# CTR-Lower-Main-Board-Rev-C-Power-3.net
KiCad netlist of a schematic drawn in Altium Designer
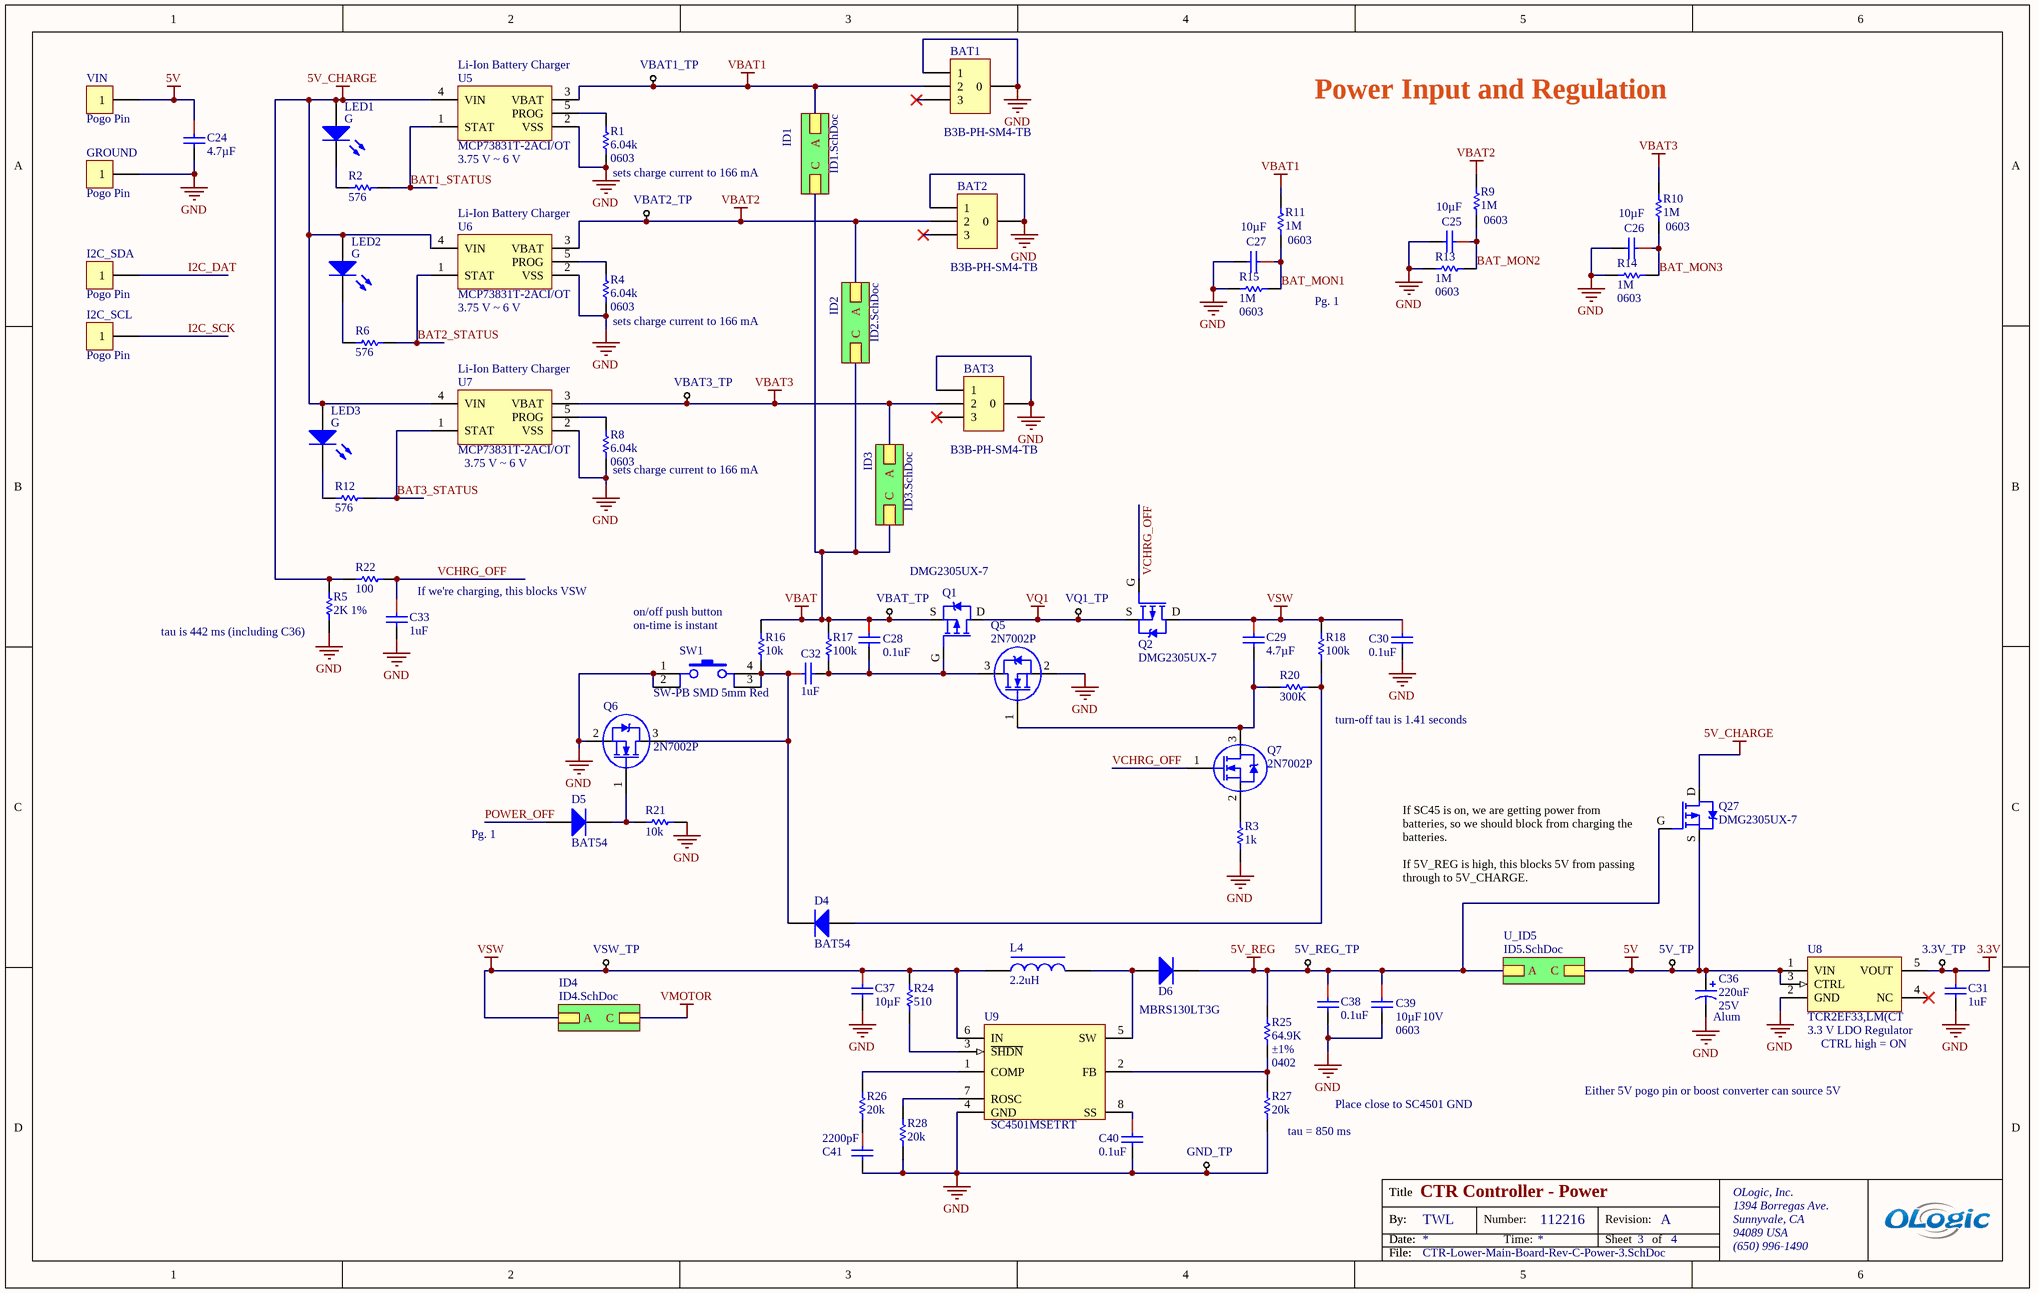
[diagram p0: CTR-Lower-Main-Board-Rev-C-Power-3.SchDoc]

(export (version "E")
  (design (tool "Eeschema 10.0.6"))
  (components
    (comp (ref "3.3V_TP")
      (value "3V")
      (footprint "TestPoint-TH 35 mil")
      (description "Test Point")
      (libsource (lib "OLogic-Misc") (part "TestPoint, small"))
    )
    (comp (ref "5V_REG_TP")
      (value "Test Point")
      (footprint "TestPoint-TH 42 mil")
      (libsource (lib "OLogic-Misc") (part "TestPoint, small"))
    )
    (comp (ref "5V_TP")
      (value "Test Point")
      (footprint "TestPoint-TH 42 mil")
      (libsource (lib "OLogic-Misc") (part "TestPoint, small"))
    )
    (comp (ref "BAT1")
      (value "B3B-PH-SM4-TB")
      (footprint "JST-B3B-PH-SM4-TB")
      (description "2mm Locking Header, 3-Pin")
      (fields
        (field (name "MANUFACTURER") "JST Sales America Inc")
        (field (name "MANUFACTURER PART NUMBER") "B3B-PH-SM4-TB(LF)(SN)(P)")
      )
      (libsource (lib "OLogic-Connectors") (part "JST-B3B-PH-SM4-TB"))
    )
    (comp (ref "BAT2")
      (value "B3B-PH-SM4-TB")
      (footprint "JST-B3B-PH-SM4-TB")
      (description "2mm Locking Header, 3-Pin")
      (fields
        (field (name "MANUFACTURER") "JST Sales America Inc")
        (field (name "MANUFACTURER PART NUMBER") "B3B-PH-SM4-TB(LF)(SN)(P)")
      )
      (libsource (lib "OLogic-Connectors") (part "JST-B3B-PH-SM4-TB"))
    )
    (comp (ref "BAT3")
      (value "B3B-PH-SM4-TB")
      (footprint "JST-B3B-PH-SM4-TB")
      (description "2mm Locking Header, 3-Pin")
      (fields
        (field (name "MANUFACTURER") "JST Sales America Inc")
        (field (name "MANUFACTURER PART NUMBER") "B3B-PH-SM4-TB(LF)(SN)(P)")
      )
      (libsource (lib "OLogic-Connectors") (part "JST-B3B-PH-SM4-TB"))
    )
    (comp (ref "C24")
      (value "4.7UF 0603")
      (footprint "CAPC0603(1608)_L")
      (fields
        (field (name "MANUFACTURER") "Taiyo Yuden")
        (field (name "MANUFACTURER PART NUMBER") "EMK107ABJ475KA-T")
        (field (name "TOLERANCE") "±10%")
        (field (name "CAPACITANCE") "4.7µF")
        (field (name "CREATOR") "osman")
      )
      (libsource (lib "OLogic-Passive") (part "CAP CER 4.7UF 16V 10% X5R 0603"))
    )
    (comp (ref "C25")
      (value "CAP 10UF 10V 10% X5R 0603")
      (footprint "CAPC0603(1608)_N")
      (description "10uF 0603")
      (fields
        (field (name "MANUFACTURER") "Samsung Electro-Mechanics America, Inc")
        (field (name "MANUFACTURER PART NUMBER") "CL10A106KP8NNNC")
        (field (name "CAPACITANCE") "10µF")
        (field (name "CREATOR") "osman")
      )
      (libsource (lib "OLogic-Passive") (part "CAP 10UF 10V 10% X5R 0603"))
    )
    (comp (ref "C26")
      (value "CAP 10UF 10V 10% X5R 0603")
      (footprint "CAPC0603(1608)_N")
      (description "10uF 0603")
      (fields
        (field (name "MANUFACTURER") "Samsung Electro-Mechanics America, Inc")
        (field (name "MANUFACTURER PART NUMBER") "CL10A106KP8NNNC")
        (field (name "CAPACITANCE") "10µF")
        (field (name "CREATOR") "osman")
      )
      (libsource (lib "OLogic-Passive") (part "CAP 10UF 10V 10% X5R 0603"))
    )
    (comp (ref "C27")
      (value "CAP 10UF 10V 10% X5R 0603")
      (footprint "CAPC0603(1608)_N")
      (description "10uF 0603")
      (fields
        (field (name "MANUFACTURER") "Samsung Electro-Mechanics America, Inc")
        (field (name "MANUFACTURER PART NUMBER") "CL10A106KP8NNNC")
        (field (name "CAPACITANCE") "10µF")
        (field (name "CREATOR") "osman")
      )
      (libsource (lib "OLogic-Passive") (part "CAP 10UF 10V 10% X5R 0603"))
    )
    (comp (ref "C28")
      (value "0.1uF")
      (footprint "CAPC0402(1005)_N")
      (description "0.1uF 0402 50V")
      (fields
        (field (name "MANUFACTURER") "TDK Corporation")
        (field (name "MANUFACTURER PART NUMBER") "CGA2B3X7R1H104K050BB")
        (field (name "CREATOR") "osman")
      )
      (libsource (lib "OLogic-Passive") (part "CAP CER 0.1UF 50V 10% X7R 0402"))
    )
    (comp (ref "C29")
      (value "4.7UF 0603")
      (footprint "CAPC0603(1608)_L")
      (fields
        (field (name "MANUFACTURER") "Taiyo Yuden")
        (field (name "MANUFACTURER PART NUMBER") "EMK107ABJ475KA-T")
        (field (name "TOLERANCE") "±10%")
        (field (name "CAPACITANCE") "4.7µF")
        (field (name "CREATOR") "osman")
      )
      (libsource (lib "OLogic-Passive") (part "CAP CER 4.7UF 16V 10% X5R 0603"))
    )
    (comp (ref "C30")
      (value "0.1uF")
      (footprint "CAPC0402(1005)_N")
      (description "0.1uF 0402 50V")
      (fields
        (field (name "MANUFACTURER") "TDK Corporation")
        (field (name "MANUFACTURER PART NUMBER") "CGA2B3X7R1H104K050BB")
        (field (name "CREATOR") "osman")
      )
      (libsource (lib "OLogic-Passive") (part "CAP CER 0.1UF 50V 10% X7R 0402"))
    )
    (comp (ref "C31")
      (value "1uF")
      (footprint "CAPC0402(1005)_N")
      (description "1UF 0402")
      (fields
        (field (name "MANUFACTURER") "TDK Corporation")
        (field (name "MANUFACTURER PART NUMBER") "C1005X5R1C105K050BC")
      )
      (libsource (lib "OLogic-Passive") (part "CAP CER 1UF 16V 10% X5R 0402"))
    )
    (comp (ref "C32")
      (value "1uF")
      (footprint "CAPC0402(1005)_N")
      (description "1UF 0402")
      (fields
        (field (name "MANUFACTURER") "TDK Corporation")
        (field (name "MANUFACTURER PART NUMBER") "C1005X5R1C105K050BC")
      )
      (libsource (lib "OLogic-Passive") (part "CAP CER 1UF 16V 10% X5R 0402"))
    )
    (comp (ref "C33")
      (value "1uF")
      (footprint "CAPC0402(1005)_N")
      (description "1UF 0402")
      (fields
        (field (name "MANUFACTURER") "TDK Corporation")
        (field (name "MANUFACTURER PART NUMBER") "C1005X5R1C105K050BC")
      )
      (libsource (lib "OLogic-Passive") (part "CAP CER 1UF 16V 10% X5R 0402"))
    )
    (comp (ref "C36")
      (value "220uF")
      (footprint "Panasonic-F-Ecap")
      (description "220uF F-SM")
      (fields
        (field (name "MANUFACTURER") "Panasonic")
        (field (name "MANUFACTURER PART NUMBER") "EEE-1EA221UP")
        (field (name "VOLTAGE RATING") "25V")
        (field (name "TEXT") "Alum")
      )
      (libsource (lib "OLogic-Passive") (part "CAP ALUM 220UF 25V 20% SMD"))
    )
    (comp (ref "C37")
      (value "CAP 10UF 10V 10% X5R 0603")
      (footprint "CAPC0603(1608)_N")
      (description "10uF 0603")
      (fields
        (field (name "MANUFACTURER") "Samsung Electro-Mechanics America, Inc")
        (field (name "MANUFACTURER PART NUMBER") "CL10A106KP8NNNC")
        (field (name "CAPACITANCE") "10µF")
        (field (name "CREATOR") "osman")
      )
      (libsource (lib "OLogic-Passive") (part "CAP 10UF 10V 10% X5R 0603"))
    )
    (comp (ref "C38")
      (value "0.1uF")
      (footprint "CAPC0402(1005)_N")
      (description "0.1uF 0402 50V")
      (fields
        (field (name "MANUFACTURER") "TDK Corporation")
        (field (name "MANUFACTURER PART NUMBER") "CGA2B3X7R1H104K050BB")
        (field (name "CREATOR") "osman")
      )
      (libsource (lib "OLogic-Passive") (part "CAP CER 0.1UF 50V 10% X7R 0402"))
    )
    (comp (ref "C39")
      (value "CAP 10UF 10V 10% X5R 0603")
      (footprint "CAPC0603(1608)_N")
      (description "10uF 0603")
      (fields
        (field (name "MANUFACTURER") "Samsung Electro-Mechanics America, Inc")
        (field (name "MANUFACTURER PART NUMBER") "CL10A106KP8NNNC")
        (field (name "VOLTAGE - RATED") "10V")
        (field (name "PACKAGE / CASE") "0603")
        (field (name "CAPACITANCE") "10µF")
        (field (name "CREATOR") "osman")
      )
      (libsource (lib "OLogic-Passive") (part "CAP 10UF 10V 10% X5R 0603"))
    )
    (comp (ref "C40")
      (value "0.1uF")
      (footprint "CAPC0402(1005)_N")
      (description "0.1uF 0402 50V")
      (fields
        (field (name "MANUFACTURER") "TDK Corporation")
        (field (name "MANUFACTURER PART NUMBER") "CGA2B3X7R1H104K050BB")
        (field (name "CREATOR") "osman")
      )
      (libsource (lib "OLogic-Passive") (part "CAP CER 0.1UF 50V 10% X7R 0402"))
    )
    (comp (ref "C41")
      (value "2200pF")
      (footprint "CAPC0402(1005)_N")
      (description "2200pF 0402")
      (fields
        (field (name "MANUFACTURER") "Yageo")
        (field (name "MANUFACTURER PART NUMBER") "CC0402KRX7R9BB222")
        (field (name "CAPACITANCE") "2200pF")
        (field (name "CREATOR") "osman")
      )
      (libsource (lib "OLogic-Passive") (part "CAP CER 2200PF 50V 10% X7R 0402"))
    )
    (comp (ref "D4")
      (value "BAT54")
      (footprint "SOT23")
      (description "Schottky Barrier Diode")
      (fields (field (name "MANUFACTURER") "Fairchild"))
      (libsource (lib "OLogic-Diode-Opto-LED") (part "BAT54"))
    )
    (comp (ref "D5")
      (value "BAT54")
      (footprint "SOT23")
      (description "Schottky Barrier Diode")
      (fields (field (name "MANUFACTURER") "Fairchild"))
      (libsource (lib "OLogic-Diode-Opto-LED") (part "BAT54"))
    )
    (comp (ref "D6")
      (value "MBRS130LT3")
      (footprint "DO-214AA")
      (description "Schottky Barrier Rectifier 1A 30V")
      (fields
        (field (name "MANUFACTURER") "ON Semiconductor")
        (field (name "MANUFACTURER PART NUMBER") "MBRS130LT3G")
      )
      (libsource (lib "OLogic-Diode-Opto-LED") (part "MBRS130LT3"))
    )
    (comp (ref "GND_TP")
      (value "GND")
      (footprint "TestPoint-TH 35 mil")
      (description "Test Point")
      (libsource (lib "OLogic-Misc") (part "TestPoint, small"))
    )
    (comp (ref "GROUND")
      (value "Pogo Pin")
      (footprint "POGO_PIN")
      (fields
        (field (name "MANUFACTURER") "Mill-Max Manufacturing Corp.")
        (field (name "MANUFACTURER PART NUMBER") "0850-0-15-20-83-14-11-0")
      )
      (libsource (lib "OLogic-Connectors") (part "0850-0-15-20-83-14-11-0"))
    )
    (comp (ref "I2C_SCL")
      (value "Pogo Pin")
      (footprint "POGO_PIN")
      (fields
        (field (name "MANUFACTURER") "Mill-Max Manufacturing Corp.")
        (field (name "MANUFACTURER PART NUMBER") "0850-0-15-20-83-14-11-0")
      )
      (libsource (lib "OLogic-Connectors") (part "0850-0-15-20-83-14-11-0"))
    )
    (comp (ref "I2C_SDA")
      (value "Pogo Pin")
      (footprint "POGO_PIN")
      (fields
        (field (name "MANUFACTURER") "Mill-Max Manufacturing Corp.")
        (field (name "MANUFACTURER PART NUMBER") "0850-0-15-20-83-14-11-0")
      )
      (libsource (lib "OLogic-Connectors") (part "0850-0-15-20-83-14-11-0"))
    )
    (comp (ref "L4")
      (value "2.2uH")
      (footprint "6x6SMINDC")
      (description "2.2uH 6x6mm")
      (fields
        (field (name "MANUFACTURER") "Taiyo Yuden")
        (field (name "MANUFACTURER PART NUMBER") "NR6028T2R2N")
      )
      (libsource (lib "OLogic-Passive") (part "INDUCTOR 2.2UH 4.2A 30% SMD"))
    )
    (comp (ref "LED1")
      (value "G")
      (footprint "SM-LED-0603")
      (description "0603 SMD GREEN LED")
      (fields
        (field (name "MANUFACTURER") "Lite-On Inc")
        (field (name "MANUFACTURER PART NUMBER") "LTST-C191KGKT")
      )
      (libsource (lib "OLogic-Diode-Opto-LED") (part "LED GREEN CLEAR THIN 0603 SMD"))
    )
    (comp (ref "LED2")
      (value "G")
      (footprint "SM-LED-0603")
      (description "0603 SMD GREEN LED")
      (fields
        (field (name "MANUFACTURER") "Lite-On Inc")
        (field (name "MANUFACTURER PART NUMBER") "LTST-C191KGKT")
      )
      (libsource (lib "OLogic-Diode-Opto-LED") (part "LED GREEN CLEAR THIN 0603 SMD"))
    )
    (comp (ref "LED3")
      (value "G")
      (footprint "SM-LED-0603")
      (description "0603 SMD GREEN LED")
      (fields
        (field (name "MANUFACTURER") "Lite-On Inc")
        (field (name "MANUFACTURER PART NUMBER") "LTST-C191KGKT")
      )
      (libsource (lib "OLogic-Diode-Opto-LED") (part "LED GREEN CLEAR THIN 0603 SMD"))
    )
    (comp (ref "Q1")
      (value "DMG2305UX")
      (footprint "DMG2305UX-7")
      (description "MOSFET P-CH 20V 4.2A SOT23")
      (fields
        (field (name "MANUFACTURER") "Diodes Incorporated")
        (field (name "MANUFACTURER PART NUMBER") "DMG2305UX-7")
        (field (name "CREATOR") "osman")
      )
      (libsource (lib "OLogic-Trans-Drivers") (part "DMG2305UX"))
    )
    (comp (ref "Q2")
      (value "DMG2305UX")
      (footprint "DMG2305UX-7")
      (description "MOSFET P-CH 20V 4.2A SOT23")
      (fields
        (field (name "MANUFACTURER") "Diodes Incorporated")
        (field (name "MANUFACTURER PART NUMBER") "DMG2305UX-7")
        (field (name "CREATOR") "osman")
      )
      (libsource (lib "OLogic-Trans-Drivers") (part "DMG2305UX"))
    )
    (comp (ref "Q5")
      (value "2N7002P")
      (footprint "SOT23")
      (description "MOSFET N-CH 60V 0.36A SOT-23")
      (fields
        (field (name "MANUFACTURER") "NXP Semiconductors")
        (field (name "MANUFACTURER PART NUMBER") "2N7002P,235")
      )
      (libsource (lib "") (part "2N7002P_2"))
    )
    (comp (ref "Q6")
      (value "2N7002P")
      (footprint "SOT23")
      (description "MOSFET N-CH 60V 0.36A SOT-23")
      (fields
        (field (name "MANUFACTURER") "NXP Semiconductors")
        (field (name "MANUFACTURER PART NUMBER") "2N7002P,235")
      )
      (libsource (lib "") (part "2N7002P_1"))
    )
    (comp (ref "Q7")
      (value "2N7002P")
      (footprint "SOT23")
      (description "MOSFET N-CH 60V 0.36A SOT-23")
      (fields
        (field (name "MANUFACTURER") "NXP Semiconductors")
        (field (name "MANUFACTURER PART NUMBER") "2N7002P,235")
      )
      (libsource (lib "OLogic-Trans-Drivers") (part "2N7002P"))
    )
    (comp (ref "Q27")
      (value "DMG2305UX")
      (footprint "DMG2305UX-7")
      (description "MOSFET P-CH 20V 4.2A SOT23")
      (fields
        (field (name "MANUFACTURER") "Diodes Incorporated")
        (field (name "MANUFACTURER PART NUMBER") "DMG2305UX-7")
        (field (name "CREATOR") "osman")
      )
      (libsource (lib "OLogic-Trans-Drivers") (part "DMG2305UX"))
    )
    (comp (ref "R1")
      (value "6.04k")
      (footprint "RESC0603(1608)_N")
      (description "6.04K 0603 RNCP0603FTD6K04")
      (fields
        (field (name "MANUFACTURER") "Stackpole Electronics Inc.")
        (field (name "MANUFACTURER PART NUMBER") "RNCP0603FTD6K04")
        (field (name "SUPPLIER DEVICE PACKAGE") "0603")
      )
      (libsource (lib "OLogic-Passive") (part "RES 6.04K OHM 1/8W 1% 0603"))
    )
    (comp (ref "R2")
      (value "576")
      (footprint "RESC0402(1005)_N")
      (description "575 0402")
      (fields
        (field (name "MANUFACTURER") "Panasonic Electronic Components")
        (field (name "MANUFACTURER PART NUMBER") "ERJ-2RKF5760X")
        (field (name "RESISTANCE (OHMS)") "576")
        (field (name "CREATOR") "osman")
      )
      (libsource (lib "OLogic-Passive") (part "RES 576 OHM 1% 1/10W 0402"))
    )
    (comp (ref "R3")
      (value "1K")
      (footprint "RESC0402(1005)_N")
      (description "1K 0402")
      (fields
        (field (name "MANUFACTURER") "Panasonic Electronic Components")
        (field (name "MANUFACTURER PART NUMBER") "ERJ-2RKF1001X")
        (field (name "RESISTANCE (OHMS)") "1k")
        (field (name "CREATOR") "osman")
      )
      (libsource (lib "OLogic-Passive") (part "RES 1K OHM 1% 1/10W 0402"))
    )
    (comp (ref "R4")
      (value "6.04k")
      (footprint "RESC0603(1608)_N")
      (description "6.04K 0603 RNCP0603FTD6K04")
      (fields
        (field (name "MANUFACTURER") "Stackpole Electronics Inc.")
        (field (name "MANUFACTURER PART NUMBER") "RNCP0603FTD6K04")
        (field (name "SUPPLIER DEVICE PACKAGE") "0603")
      )
      (libsource (lib "OLogic-Passive") (part "RES 6.04K OHM 1/8W 1% 0603"))
    )
    (comp (ref "R5")
      (value "2K 1%")
      (footprint "RESC0402(1005)_N")
      (description "2K 1% 0402")
      (fields
        (field (name "MANUFACTURER") "Panasonic Electronic Components")
        (field (name "MANUFACTURER PART NUMBER") "ERJ-2RKF2001X")
      )
      (libsource (lib "OLogic-Passive") (part "RES 2K OHM 1% 1/10W 0402"))
    )
    (comp (ref "R6")
      (value "576")
      (footprint "RESC0402(1005)_N")
      (description "575 0402")
      (fields
        (field (name "MANUFACTURER") "Panasonic Electronic Components")
        (field (name "MANUFACTURER PART NUMBER") "ERJ-2RKF5760X")
        (field (name "RESISTANCE (OHMS)") "576")
        (field (name "CREATOR") "osman")
      )
      (libsource (lib "OLogic-Passive") (part "RES 576 OHM 1% 1/10W 0402"))
    )
    (comp (ref "R8")
      (value "6.04k")
      (footprint "RESC0603(1608)_N")
      (description "6.04K 0603 RNCP0603FTD6K04")
      (fields
        (field (name "MANUFACTURER") "Stackpole Electronics Inc.")
        (field (name "MANUFACTURER PART NUMBER") "RNCP0603FTD6K04")
        (field (name "SUPPLIER DEVICE PACKAGE") "0603")
      )
      (libsource (lib "OLogic-Passive") (part "RES 6.04K OHM 1/8W 1% 0603"))
    )
    (comp (ref "R9")
      (value "1M")
      (footprint "RESC0603(1608)_N")
      (description "1M 0603")
      (fields
        (field (name "MANUFACTURER") "Panasonic Electronic Components")
        (field (name "MANUFACTURER PART NUMBER") "ERJ-3EKF1004V")
        (field (name "SUPPLIER DEVICE PACKAGE") "0603")
      )
      (libsource (lib "OLogic-Passive") (part "RES 1M OHM 1/10W 1% 0603 SMD"))
    )
    (comp (ref "R10")
      (value "1M")
      (footprint "RESC0603(1608)_N")
      (description "1M 0603")
      (fields
        (field (name "MANUFACTURER") "Panasonic Electronic Components")
        (field (name "MANUFACTURER PART NUMBER") "ERJ-3EKF1004V")
        (field (name "SUPPLIER DEVICE PACKAGE") "0603")
      )
      (libsource (lib "OLogic-Passive") (part "RES 1M OHM 1/10W 1% 0603 SMD"))
    )
    (comp (ref "R11")
      (value "1M")
      (footprint "RESC0603(1608)_N")
      (description "1M 0603")
      (fields
        (field (name "MANUFACTURER") "Panasonic Electronic Components")
        (field (name "MANUFACTURER PART NUMBER") "ERJ-3EKF1004V")
        (field (name "SUPPLIER DEVICE PACKAGE") "0603")
      )
      (libsource (lib "OLogic-Passive") (part "RES 1M OHM 1/10W 1% 0603 SMD"))
    )
    (comp (ref "R12")
      (value "576")
      (footprint "RESC0402(1005)_N")
      (description "575 0402")
      (fields
        (field (name "MANUFACTURER") "Panasonic Electronic Components")
        (field (name "MANUFACTURER PART NUMBER") "ERJ-2RKF5760X")
        (field (name "RESISTANCE (OHMS)") "576")
        (field (name "CREATOR") "osman")
      )
      (libsource (lib "OLogic-Passive") (part "RES 576 OHM 1% 1/10W 0402"))
    )
    (comp (ref "R13")
      (value "1M")
      (footprint "RESC0603(1608)_N")
      (description "1M 0603")
      (fields
        (field (name "MANUFACTURER") "Panasonic Electronic Components")
        (field (name "MANUFACTURER PART NUMBER") "ERJ-3EKF1004V")
        (field (name "SUPPLIER DEVICE PACKAGE") "0603")
      )
      (libsource (lib "OLogic-Passive") (part "RES 1M OHM 1/10W 1% 0603 SMD"))
    )
    (comp (ref "R14")
      (value "1M")
      (footprint "RESC0603(1608)_N")
      (description "1M 0603")
      (fields
        (field (name "MANUFACTURER") "Panasonic Electronic Components")
        (field (name "MANUFACTURER PART NUMBER") "ERJ-3EKF1004V")
        (field (name "SUPPLIER DEVICE PACKAGE") "0603")
      )
      (libsource (lib "OLogic-Passive") (part "RES 1M OHM 1/10W 1% 0603 SMD"))
    )
    (comp (ref "R15")
      (value "1M")
      (footprint "RESC0603(1608)_N")
      (description "1M 0603")
      (fields
        (field (name "MANUFACTURER") "Panasonic Electronic Components")
        (field (name "MANUFACTURER PART NUMBER") "ERJ-3EKF1004V")
        (field (name "SUPPLIER DEVICE PACKAGE") "0603")
      )
      (libsource (lib "OLogic-Passive") (part "RES 1M OHM 1/10W 1% 0603 SMD"))
    )
    (comp (ref "R16")
      (value "10K")
      (footprint "RESC0402(1005)_N")
      (description "10K 0402")
      (fields
        (field (name "MANUFACTURER") "Panasonic Electronic Components")
        (field (name "MANUFACTURER PART NUMBER") "ERJ-2RKF1002X")
        (field (name "RESISTANCE (OHMS)") "10k")
        (field (name "CREATOR") "osman")
      )
      (libsource (lib "OLogic-Passive") (part "RES 10K OHM 1% 1/10W 0402"))
    )
    (comp (ref "R17")
      (value "100K 0402")
      (footprint "RESC0402(1005)_N")
      (fields
        (field (name "MANUFACTURER") "Panasonic Electronic Components")
        (field (name "MANUFACTURER PART NUMBER") "ERJ-2RKF1003X")
        (field (name "TOLERANCE") "±1%")
        (field (name "RESISTANCE (OHMS)") "100k")
        (field (name "CREATOR") "osman")
      )
      (libsource (lib "OLogic-Passive") (part "RES 100K OHM 1% 1/10W 0402"))
    )
    (comp (ref "R18")
      (value "100K 0402")
      (footprint "RESC0402(1005)_N")
      (fields
        (field (name "MANUFACTURER") "Panasonic Electronic Components")
        (field (name "MANUFACTURER PART NUMBER") "ERJ-2RKF1003X")
        (field (name "TOLERANCE") "±1%")
        (field (name "RESISTANCE (OHMS)") "100k")
        (field (name "CREATOR") "osman")
      )
      (libsource (lib "OLogic-Passive") (part "RES 100K OHM 1% 1/10W 0402"))
    )
    (comp (ref "R20")
      (value "300K")
      (footprint "RESC0402(1005)_N")
      (description "300K 0402")
      (fields
        (field (name "MANUFACTURER") "Panasonic Electronic Components")
        (field (name "MANUFACTURER PART NUMBER") "ERJ-2RKF3003X")
      )
      (libsource (lib "OLogic-Passive") (part "RES 300K OHM 1% 1/10W 0402"))
    )
    (comp (ref "R21")
      (value "10K")
      (footprint "RESC0402(1005)_N")
      (description "10K 0402")
      (fields
        (field (name "MANUFACTURER") "Panasonic Electronic Components")
        (field (name "MANUFACTURER PART NUMBER") "ERJ-2RKF1002X")
        (field (name "RESISTANCE (OHMS)") "10k")
        (field (name "CREATOR") "osman")
      )
      (libsource (lib "OLogic-Passive") (part "RES 10K OHM 1% 1/10W 0402"))
    )
    (comp (ref "R22")
      (value "100 0402")
      (footprint "RESC0402(1005)_N")
      (fields
        (field (name "MANUFACTURER") "Panasonic Electronic Components")
        (field (name "MANUFACTURER PART NUMBER") "ERJ-2RKF1000X")
        (field (name "TOLERANCE") "±1%")
        (field (name "RESISTANCE (OHMS)") "100")
        (field (name "CREATOR") "osman")
      )
      (libsource (lib "OLogic-Passive") (part "RES 100 OHM 1% 1/10W 0402"))
    )
    (comp (ref "R24")
      (value "510")
      (footprint "RESC0603(1608)_N")
      (description "510 0603")
      (fields
        (field (name "MANUFACTURER") "Panasonic Electronic Components")
        (field (name "MANUFACTURER PART NUMBER") "ERJ-3EKF5100V")
      )
      (libsource (lib "OLogic-Passive") (part "RES 510 OHM 1/10W 1% 0603 SMD"))
    )
    (comp (ref "R25")
      (value "64.9K")
      (footprint "RESC0402(1005)_N")
      (description "RES 64.9K OHM 1% 1/10W 0402")
      (fields
        (field (name "MANUFACTURER") "Panasonic Electronic Components")
        (field (name "MANUFACTURER PART NUMBER") "ERJ-2RKF6492X")
        (field (name "TOLERANCE") "±1%")
        (field (name "SUPPLIER DEVICE PACKAGE") "0402")
      )
      (libsource (lib "OLogic-Passive") (part "RES 64.9K OHM 1% 1/10W 0402"))
    )
    (comp (ref "R26")
      (value "20K 0402")
      (footprint "RESC0402(1005)_N")
      (fields
        (field (name "MANUFACTURER") "Panasonic Electronic Components")
        (field (name "MANUFACTURER PART NUMBER") "ERJ-2RKF2002X")
        (field (name "RESISTANCE (OHMS)") "20k")
        (field (name "TOLERANCE") "±1%")
      )
      (libsource (lib "OLogic-Passive") (part "RES 20K OHM 1% 1/10W 0402"))
    )
    (comp (ref "R27")
      (value "20K 0402")
      (footprint "RESC0402(1005)_N")
      (fields
        (field (name "MANUFACTURER") "Panasonic Electronic Components")
        (field (name "MANUFACTURER PART NUMBER") "ERJ-2RKF2002X")
        (field (name "TOLERANCE") "±1%")
        (field (name "RESISTANCE (OHMS)") "20k")
      )
      (libsource (lib "OLogic-Passive") (part "RES 20K OHM 1% 1/10W 0402"))
    )
    (comp (ref "R28")
      (value "20K 0402")
      (footprint "RESC0402(1005)_N")
      (fields
        (field (name "MANUFACTURER") "Panasonic Electronic Components")
        (field (name "MANUFACTURER PART NUMBER") "ERJ-2RKF2002X")
        (field (name "RESISTANCE (OHMS)") "20k")
        (field (name "TOLERANCE") "±1%")
      )
      (libsource (lib "OLogic-Passive") (part "RES 20K OHM 1% 1/10W 0402"))
    )
    (comp (ref "SW1")
      (value "SW-PB SMD 5mm Red")
      (footprint "SW TACT Red 6mm x 6mm")
      (description "SWITCH TACTILE SPST-NO 0.05A 12V")
      (fields
        (field (name "MANUFACTURER") "C&K Components")
        (field (name "MANUFACTURER PART NUMBER") "PTS645SK50SMTR92 LFS")
        (field (name "PUBLISHER") "Altium Limited")
      )
      (libsource (lib "OLogic-Switches") (part "SW-PB SMD 5mm Red"))
    )
    (comp (ref "U5")
      (value "Li-Ion Battery Charger")
      (footprint "SOT23-5")
      (fields
        (field (name "MPN") "MCP73831T")
        (field (name "MANUFACTURER") "Microchip")
        (field (name "MANUFACTURER PART NUMBER") "MCP73831T-2ACI/OT")
        (field (name "VOLTAGE - SUPPLY") "3.75 V ~ 6 V")
      )
      (libsource (lib "OLogic-Misc") (part "MCP73831"))
    )
    (comp (ref "U6")
      (value "Li-Ion Battery Charger")
      (footprint "SOT23-5")
      (fields
        (field (name "MPN") "MCP73831T")
        (field (name "MANUFACTURER") "Microchip")
        (field (name "MANUFACTURER PART NUMBER") "MCP73831T-2ACI/OT")
        (field (name "VOLTAGE - SUPPLY") "3.75 V ~ 6 V")
      )
      (libsource (lib "OLogic-Misc") (part "MCP73831"))
    )
    (comp (ref "U7")
      (value "Li-Ion Battery Charger")
      (footprint "SOT23-5")
      (fields
        (field (name "MPN") "MCP73831T")
        (field (name "MANUFACTURER") "Microchip")
        (field (name "MANUFACTURER PART NUMBER") "MCP73831T-2ACI/OT")
        (field (name "VOLTAGE - SUPPLY") "3.75 V ~ 6 V")
      )
      (libsource (lib "OLogic-Misc") (part "MCP73831"))
    )
    (comp (ref "U8")
      (value "3.3 V LDO Regulator")
      (footprint "TCRFEF")
      (description "IC REG LDO 3.3V 0.2A ESV")
      (fields
        (field (name "MANUFACTURER") "Toshiba Semiconductor and Storage")
        (field (name "MANUFACTURER PART NUMBER") "TCR2EF33,LM(CT")
        (field (name "CREATOR") "osman")
      )
      (libsource (lib "OLogic-Reg-Convert") (part "TCR2EF33"))
    )
    (comp (ref "U9")
      (value "SC4501")
      (footprint "SC4501")
      (description "2A Switching Step-Up Regulator")
      (fields
        (field (name "MANUFACTURER") "Semtech Corporation")
        (field (name "MANUFACTURER PART NUMBER") "SC4501MSETRT")
      )
      (libsource (lib "OLogic-Reg-Convert") (part "SC4501"))
    )
    (comp (ref "VBAT1_TP")
      (value "Test Point")
      (footprint "TestPoint-TH 42 mil")
      (libsource (lib "OLogic-Misc") (part "TestPoint, small"))
    )
    (comp (ref "VBAT2_TP")
      (value "Test Point")
      (footprint "TestPoint-TH 42 mil")
      (libsource (lib "OLogic-Misc") (part "TestPoint, small"))
    )
    (comp (ref "VBAT3_TP")
      (value "Test Point")
      (footprint "TestPoint-TH 42 mil")
      (libsource (lib "OLogic-Misc") (part "TestPoint, small"))
    )
    (comp (ref "VBAT_TP")
      (value "Test Point")
      (footprint "TestPoint-TH 42 mil")
      (libsource (lib "OLogic-Misc") (part "TestPoint, small"))
    )
    (comp (ref "VIN")
      (value "Pogo Pin")
      (footprint "POGO_PIN")
      (fields
        (field (name "MANUFACTURER") "Mill-Max Manufacturing Corp.")
        (field (name "MANUFACTURER PART NUMBER") "0850-0-15-20-83-14-11-0")
      )
      (libsource (lib "OLogic-Connectors") (part "0850-0-15-20-83-14-11-0"))
    )
    (comp (ref "VQ1_TP")
      (value "Test Point")
      (footprint "TestPoint-TH 42 mil")
      (libsource (lib "OLogic-Misc") (part "TestPoint, small"))
    )
    (comp (ref "VSW_TP")
      (value "Test Point")
      (footprint "TestPoint-TH 42 mil")
      (libsource (lib "OLogic-Misc") (part "TestPoint, small"))
    )
  )
  (nets
    (net (code "1") (name "/BAT1_STATUS") (class "Default")
      (node (ref "R2") (pin "2") (pinfunction "2_2") (pintype "passive"))
      (node (ref "U5") (pin "1") (pinfunction "STAT_1") (pintype "passive"))
    )
    (net (code "2") (name "/BAT2_STATUS") (class "Default")
      (node (ref "R6") (pin "2") (pinfunction "2_2") (pintype "passive"))
      (node (ref "U6") (pin "1") (pinfunction "STAT_1") (pintype "passive"))
    )
    (net (code "3") (name "/BAT3_STATUS") (class "Default")
      (node (ref "R12") (pin "2") (pinfunction "2_2") (pintype "passive"))
      (node (ref "U7") (pin "1") (pinfunction "STAT_1") (pintype "passive"))
    )
    (net (code "4") (name "/BAT_MON1") (class "Default")
      (node (ref "C27") (pin "1") (pinfunction "1_1") (pintype "passive"))
      (node (ref "R11") (pin "1") (pinfunction "1_1") (pintype "passive"))
      (node (ref "R15") (pin "1") (pinfunction "1_1") (pintype "passive"))
    )
    (net (code "5") (name "/BAT_MON2") (class "Default")
      (node (ref "C25") (pin "1") (pinfunction "1_1") (pintype "passive"))
      (node (ref "R13") (pin "1") (pinfunction "1_1") (pintype "passive"))
      (node (ref "R9") (pin "1") (pinfunction "1_1") (pintype "passive"))
    )
    (net (code "6") (name "/BAT_MON3") (class "Default")
      (node (ref "C26") (pin "1") (pinfunction "1_1") (pintype "passive"))
      (node (ref "R10") (pin "1") (pinfunction "1_1") (pintype "passive"))
      (node (ref "R14") (pin "1") (pinfunction "1_1") (pintype "passive"))
    )
    (net (code "7") (name "/I2C_DAT") (class "Default")
      (node (ref "I2C_SDA") (pin "1") (pinfunction "1_1") (pintype "passive"))
    )
    (net (code "8") (name "/I2C_SCK") (class "Default")
      (node (ref "I2C_SCL") (pin "1") (pinfunction "1_1") (pintype "passive"))
    )
    (net (code "9") (name "/POWER_OFF") (class "Default")
      (node (ref "D5") (pin "1") (pinfunction "A_1") (pintype "passive"))
    )
    (net (code "10") (name "/VCHRG_OFF") (class "Default")
      (node (ref "C33") (pin "1") (pinfunction "1_1") (pintype "passive"))
      (node (ref "Q2") (pin "G") (pinfunction "G_G") (pintype "passive"))
      (node (ref "Q7") (pin "1") (pinfunction "G_1") (pintype "passive"))
      (node (ref "R22") (pin "1") (pinfunction "1_1") (pintype "passive"))
    )
    (net (code "11") (name "3.3V") (class "Default")
      (node (ref "3.3V_TP") (pin "1") (pinfunction "1_1") (pintype "passive"))
      (node (ref "C31") (pin "1") (pinfunction "1_1") (pintype "passive"))
      (node (ref "U8") (pin "5") (pinfunction "VOUT_5") (pintype "power_in"))
    )
    (net (code "12") (name "5V") (class "Default")
      (node (ref "5V_TP") (pin "1") (pinfunction "1_1") (pintype "passive"))
      (node (ref "C24") (pin "1") (pinfunction "1_1") (pintype "passive"))
      (node (ref "C36") (pin "1") (pinfunction "1_1") (pintype "passive"))
      (node (ref "Q27") (pin "S") (pinfunction "S_S") (pintype "passive"))
      (node (ref "U8") (pin "1") (pinfunction "VIN_1") (pintype "power_in"))
      (node (ref "U8") (pin "3") (pinfunction "CTRL_3") (pintype "input"))
      (node (ref "VIN") (pin "1") (pinfunction "1_1") (pintype "passive"))
    )
    (net (code "13") (name "5V_CHARGE") (class "Default")
      (node (ref "LED1") (pin "1") (pinfunction "1_1") (pintype "passive"))
      (node (ref "LED2") (pin "1") (pinfunction "1_1") (pintype "passive"))
      (node (ref "LED3") (pin "1") (pinfunction "1_1") (pintype "passive"))
      (node (ref "Q27") (pin "D") (pinfunction "D_D") (pintype "passive"))
      (node (ref "R22") (pin "2") (pinfunction "2_2") (pintype "passive"))
      (node (ref "R5") (pin "2") (pinfunction "2_2") (pintype "passive"))
      (node (ref "U5") (pin "4") (pinfunction "VIN_4") (pintype "passive"))
      (node (ref "U6") (pin "4") (pinfunction "VIN_4") (pintype "passive"))
      (node (ref "U7") (pin "4") (pinfunction "VIN_4") (pintype "passive"))
    )
    (net (code "14") (name "5V_REG") (class "Default")
      (node (ref "5V_REG_TP") (pin "1") (pinfunction "1_1") (pintype "passive"))
      (node (ref "C38") (pin "1") (pinfunction "1_1") (pintype "passive"))
      (node (ref "C39") (pin "1") (pinfunction "1_1") (pintype "passive"))
      (node (ref "D6") (pin "2") (pinfunction "K_2") (pintype "passive"))
      (node (ref "Q27") (pin "G") (pinfunction "G_G") (pintype "passive"))
      (node (ref "R25") (pin "2") (pinfunction "2_2") (pintype "passive"))
    )
    (net (code "15") (name "GND") (class "Default")
      (node (ref "BAT1") (pin "0") (pinfunction "0_0") (pintype "passive"))
      (node (ref "BAT1") (pin "1") (pinfunction "1_1") (pintype "passive"))
      (node (ref "BAT2") (pin "0") (pinfunction "0_0") (pintype "passive"))
      (node (ref "BAT2") (pin "1") (pinfunction "1_1") (pintype "passive"))
      (node (ref "BAT3") (pin "0") (pinfunction "0_0") (pintype "passive"))
      (node (ref "BAT3") (pin "1") (pinfunction "1_1") (pintype "passive"))
      (node (ref "C24") (pin "2") (pinfunction "2_2") (pintype "passive"))
      (node (ref "C25") (pin "2") (pinfunction "2_2") (pintype "passive"))
      (node (ref "C26") (pin "2") (pinfunction "2_2") (pintype "passive"))
      (node (ref "C27") (pin "2") (pinfunction "2_2") (pintype "passive"))
      (node (ref "C30") (pin "2") (pinfunction "2_2") (pintype "passive"))
      (node (ref "C31") (pin "2") (pinfunction "2_2") (pintype "passive"))
      (node (ref "C33") (pin "2") (pinfunction "2_2") (pintype "passive"))
      (node (ref "C36") (pin "2") (pinfunction "2_2") (pintype "passive"))
      (node (ref "C37") (pin "2") (pinfunction "2_2") (pintype "passive"))
      (node (ref "C38") (pin "2") (pinfunction "2_2") (pintype "passive"))
      (node (ref "C39") (pin "2") (pinfunction "2_2") (pintype "passive"))
      (node (ref "C40") (pin "2") (pinfunction "2_2") (pintype "passive"))
      (node (ref "C41") (pin "2") (pinfunction "2_2") (pintype "passive"))
      (node (ref "GND_TP") (pin "1") (pinfunction "1_1") (pintype "passive"))
      (node (ref "GROUND") (pin "1") (pinfunction "1_1") (pintype "passive"))
      (node (ref "Q5") (pin "2") (pinfunction "S_2") (pintype "passive"))
      (node (ref "Q6") (pin "2") (pinfunction "S_2") (pintype "passive"))
      (node (ref "R1") (pin "1") (pinfunction "1_1") (pintype "passive"))
      (node (ref "R13") (pin "2") (pinfunction "2_2") (pintype "passive"))
      (node (ref "R14") (pin "2") (pinfunction "2_2") (pintype "passive"))
      (node (ref "R15") (pin "2") (pinfunction "2_2") (pintype "passive"))
      (node (ref "R21") (pin "1") (pinfunction "1_1") (pintype "passive"))
      (node (ref "R27") (pin "1") (pinfunction "1_1") (pintype "passive"))
      (node (ref "R28") (pin "2") (pinfunction "2_2") (pintype "passive"))
      (node (ref "R3") (pin "1") (pinfunction "1_1") (pintype "passive"))
      (node (ref "R4") (pin "1") (pinfunction "1_1") (pintype "passive"))
      (node (ref "R5") (pin "1") (pinfunction "1_1") (pintype "passive"))
      (node (ref "R8") (pin "1") (pinfunction "1_1") (pintype "passive"))
      (node (ref "SW1") (pin "1") (pinfunction "1_1") (pintype "passive"))
      (node (ref "SW1") (pin "2") (pinfunction "2_2") (pintype "passive"))
      (node (ref "U5") (pin "2") (pinfunction "VSS_2") (pintype "passive"))
      (node (ref "U6") (pin "2") (pinfunction "VSS_2") (pintype "passive"))
      (node (ref "U7") (pin "2") (pinfunction "VSS_2") (pintype "passive"))
      (node (ref "U8") (pin "2") (pinfunction "GND_2") (pintype "power_in"))
      (node (ref "U9") (pin "4") (pinfunction "GND_4") (pintype "power_in"))
    )
    (net (code "16") (name "Net-(C41-Pad1)") (class "Default")
      (node (ref "C41") (pin "1") (pinfunction "1_1") (pintype "passive"))
      (node (ref "R26") (pin "2") (pinfunction "2_2") (pintype "passive"))
    )
    (net (code "17") (name "Net-(D4-A)") (class "Default")
      (node (ref "D4") (pin "1") (pinfunction "A_1") (pintype "passive"))
      (node (ref "R18") (pin "1") (pinfunction "1_1") (pintype "passive"))
      (node (ref "R20") (pin "1") (pinfunction "1_1") (pintype "passive"))
    )
    (net (code "18") (name "Net-(D4-K)") (class "Default")
      (node (ref "C32") (pin "1") (pinfunction "1_1") (pintype "passive"))
      (node (ref "D4") (pin "3") (pinfunction "K_3") (pintype "passive"))
      (node (ref "Q6") (pin "3") (pinfunction "D_3") (pintype "passive"))
      (node (ref "R16") (pin "1") (pinfunction "1_1") (pintype "passive"))
      (node (ref "SW1") (pin "3") (pinfunction "3_3") (pintype "passive"))
      (node (ref "SW1") (pin "4") (pinfunction "4_4") (pintype "passive"))
    )
    (net (code "19") (name "Net-(D5-K)") (class "Default")
      (node (ref "D5") (pin "3") (pinfunction "K_3") (pintype "passive"))
      (node (ref "Q6") (pin "1") (pinfunction "G_1") (pintype "passive"))
      (node (ref "R21") (pin "2") (pinfunction "2_2") (pintype "passive"))
    )
    (net (code "20") (name "Net-(D6-A)") (class "Default")
      (node (ref "D6") (pin "1") (pinfunction "A_1") (pintype "passive"))
      (node (ref "L4") (pin "2") (pinfunction "2_2") (pintype "passive"))
      (node (ref "U9") (pin "5") (pinfunction "SW_5") (pintype "passive"))
    )
    (net (code "21") (name "Net-(LED1-Pad2)") (class "Default")
      (node (ref "LED1") (pin "2") (pinfunction "2_2") (pintype "passive"))
      (node (ref "R2") (pin "1") (pinfunction "1_1") (pintype "passive"))
    )
    (net (code "22") (name "Net-(LED2-Pad2)") (class "Default")
      (node (ref "LED2") (pin "2") (pinfunction "2_2") (pintype "passive"))
      (node (ref "R6") (pin "1") (pinfunction "1_1") (pintype "passive"))
    )
    (net (code "23") (name "Net-(LED3-Pad2)") (class "Default")
      (node (ref "LED3") (pin "2") (pinfunction "2_2") (pintype "passive"))
      (node (ref "R12") (pin "1") (pinfunction "1_1") (pintype "passive"))
    )
    (net (code "24") (name "Net-(Q5-D)") (class "Default")
      (node (ref "C28") (pin "2") (pinfunction "2_2") (pintype "passive"))
      (node (ref "C32") (pin "2") (pinfunction "2_2") (pintype "passive"))
      (node (ref "Q1") (pin "G") (pinfunction "G_G") (pintype "passive"))
      (node (ref "Q5") (pin "3") (pinfunction "D_3") (pintype "passive"))
      (node (ref "R17") (pin "1") (pinfunction "1_1") (pintype "passive"))
    )
    (net (code "25") (name "Net-(Q5-G)") (class "Default")
      (node (ref "C29") (pin "2") (pinfunction "2_2") (pintype "passive"))
      (node (ref "Q5") (pin "1") (pinfunction "G_1") (pintype "passive"))
      (node (ref "Q7") (pin "3") (pinfunction "D_3") (pintype "passive"))
      (node (ref "R20") (pin "2") (pinfunction "2_2") (pintype "passive"))
    )
    (net (code "26") (name "Net-(Q7-S)") (class "Default")
      (node (ref "Q7") (pin "2") (pinfunction "S_2") (pintype "passive"))
      (node (ref "R3") (pin "2") (pinfunction "2_2") (pintype "passive"))
    )
    (net (code "27") (name "Net-(U5-PROG)") (class "Default")
      (node (ref "R1") (pin "2") (pinfunction "2_2") (pintype "passive"))
      (node (ref "U5") (pin "5") (pinfunction "PROG_5") (pintype "passive"))
    )
    (net (code "28") (name "Net-(U6-PROG)") (class "Default")
      (node (ref "R4") (pin "2") (pinfunction "2_2") (pintype "passive"))
      (node (ref "U6") (pin "5") (pinfunction "PROG_5") (pintype "passive"))
    )
    (net (code "29") (name "Net-(U7-PROG)") (class "Default")
      (node (ref "R8") (pin "2") (pinfunction "2_2") (pintype "passive"))
      (node (ref "U7") (pin "5") (pinfunction "PROG_5") (pintype "passive"))
    )
    (net (code "30") (name "Net-(U9-COMP)") (class "Default")
      (node (ref "R26") (pin "1") (pinfunction "1_1") (pintype "passive"))
      (node (ref "U9") (pin "1") (pinfunction "COMP_1") (pintype "passive"))
    )
    (net (code "31") (name "Net-(U9-FB)") (class "Default")
      (node (ref "R25") (pin "1") (pinfunction "1_1") (pintype "passive"))
      (node (ref "R27") (pin "2") (pinfunction "2_2") (pintype "passive"))
      (node (ref "U9") (pin "2") (pinfunction "FB_2") (pintype "passive"))
    )
    (net (code "32") (name "Net-(U9-ROSC)") (class "Default")
      (node (ref "R28") (pin "1") (pinfunction "1_1") (pintype "passive"))
      (node (ref "U9") (pin "7") (pinfunction "ROSC_7") (pintype "passive"))
    )
    (net (code "33") (name "Net-(U9-SS)") (class "Default")
      (node (ref "C40") (pin "1") (pinfunction "1_1") (pintype "passive"))
      (node (ref "U9") (pin "8") (pinfunction "SS_8") (pintype "passive"))
    )
    (net (code "34") (name "Net-(U9-~{SHDN})") (class "Default")
      (node (ref "R24") (pin "1") (pinfunction "1_1") (pintype "passive"))
      (node (ref "U9") (pin "3") (pinfunction "~{SHDN}_3") (pintype "input"))
    )
    (net (code "35") (name "VBAT") (class "Default")
      (node (ref "C28") (pin "1") (pinfunction "1_1") (pintype "passive"))
      (node (ref "Q1") (pin "S") (pinfunction "S_S") (pintype "passive"))
      (node (ref "R16") (pin "2") (pinfunction "2_2") (pintype "passive"))
      (node (ref "R17") (pin "2") (pinfunction "2_2") (pintype "passive"))
      (node (ref "VBAT_TP") (pin "1") (pinfunction "1_1") (pintype "passive"))
    )
    (net (code "36") (name "VBAT1") (class "Default")
      (node (ref "BAT1") (pin "2") (pinfunction "2_2") (pintype "passive"))
      (node (ref "R11") (pin "2") (pinfunction "2_2") (pintype "passive"))
      (node (ref "U5") (pin "3") (pinfunction "VBAT_3") (pintype "passive"))
      (node (ref "VBAT1_TP") (pin "1") (pinfunction "1_1") (pintype "passive"))
    )
    (net (code "37") (name "VBAT2") (class "Default")
      (node (ref "BAT2") (pin "2") (pinfunction "2_2") (pintype "passive"))
      (node (ref "R9") (pin "2") (pinfunction "2_2") (pintype "passive"))
      (node (ref "U6") (pin "3") (pinfunction "VBAT_3") (pintype "passive"))
      (node (ref "VBAT2_TP") (pin "1") (pinfunction "1_1") (pintype "passive"))
    )
    (net (code "38") (name "VBAT3") (class "Default")
      (node (ref "BAT3") (pin "2") (pinfunction "2_2") (pintype "passive"))
      (node (ref "R10") (pin "2") (pinfunction "2_2") (pintype "passive"))
      (node (ref "U7") (pin "3") (pinfunction "VBAT_3") (pintype "passive"))
      (node (ref "VBAT3_TP") (pin "1") (pinfunction "1_1") (pintype "passive"))
    )
    (net (code "40") (name "VQ1") (class "Default")
      (node (ref "Q1") (pin "D") (pinfunction "D_D") (pintype "passive"))
      (node (ref "Q2") (pin "S") (pinfunction "S_S") (pintype "passive"))
      (node (ref "VQ1_TP") (pin "1") (pinfunction "1_1") (pintype "passive"))
    )
    (net (code "41") (name "VSW") (class "Default")
      (node (ref "C29") (pin "1") (pinfunction "1_1") (pintype "passive"))
      (node (ref "C30") (pin "1") (pinfunction "1_1") (pintype "passive"))
      (node (ref "C37") (pin "1") (pinfunction "1_1") (pintype "passive"))
      (node (ref "L4") (pin "1") (pinfunction "1_1") (pintype "passive"))
      (node (ref "Q2") (pin "D") (pinfunction "D_D") (pintype "passive"))
      (node (ref "R18") (pin "2") (pinfunction "2_2") (pintype "passive"))
      (node (ref "R24") (pin "2") (pinfunction "2_2") (pintype "passive"))
      (node (ref "U9") (pin "6") (pinfunction "IN_6") (pintype "power_in"))
      (node (ref "VSW_TP") (pin "1") (pinfunction "1_1") (pintype "passive"))
    )
    (net (code "42") (name "unconnected-(BAT1-Pad3)") (class "Default")
      (node (ref "BAT1") (pin "3") (pinfunction "3_3") (pintype "passive+no_connect"))
    )
    (net (code "43") (name "unconnected-(BAT2-Pad3)") (class "Default")
      (node (ref "BAT2") (pin "3") (pinfunction "3_3") (pintype "passive+no_connect"))
    )
    (net (code "44") (name "unconnected-(BAT3-Pad3)") (class "Default")
      (node (ref "BAT3") (pin "3") (pinfunction "3_3") (pintype "passive+no_connect"))
    )
    (net (code "45") (name "unconnected-(U8-NC-Pad4)") (class "Default")
      (node (ref "U8") (pin "4") (pinfunction "NC_4") (pintype "passive+no_connect"))
    )
  )
)
